# UpConverter.net
KiCad netlist of a schematic drawn in Altium Designer
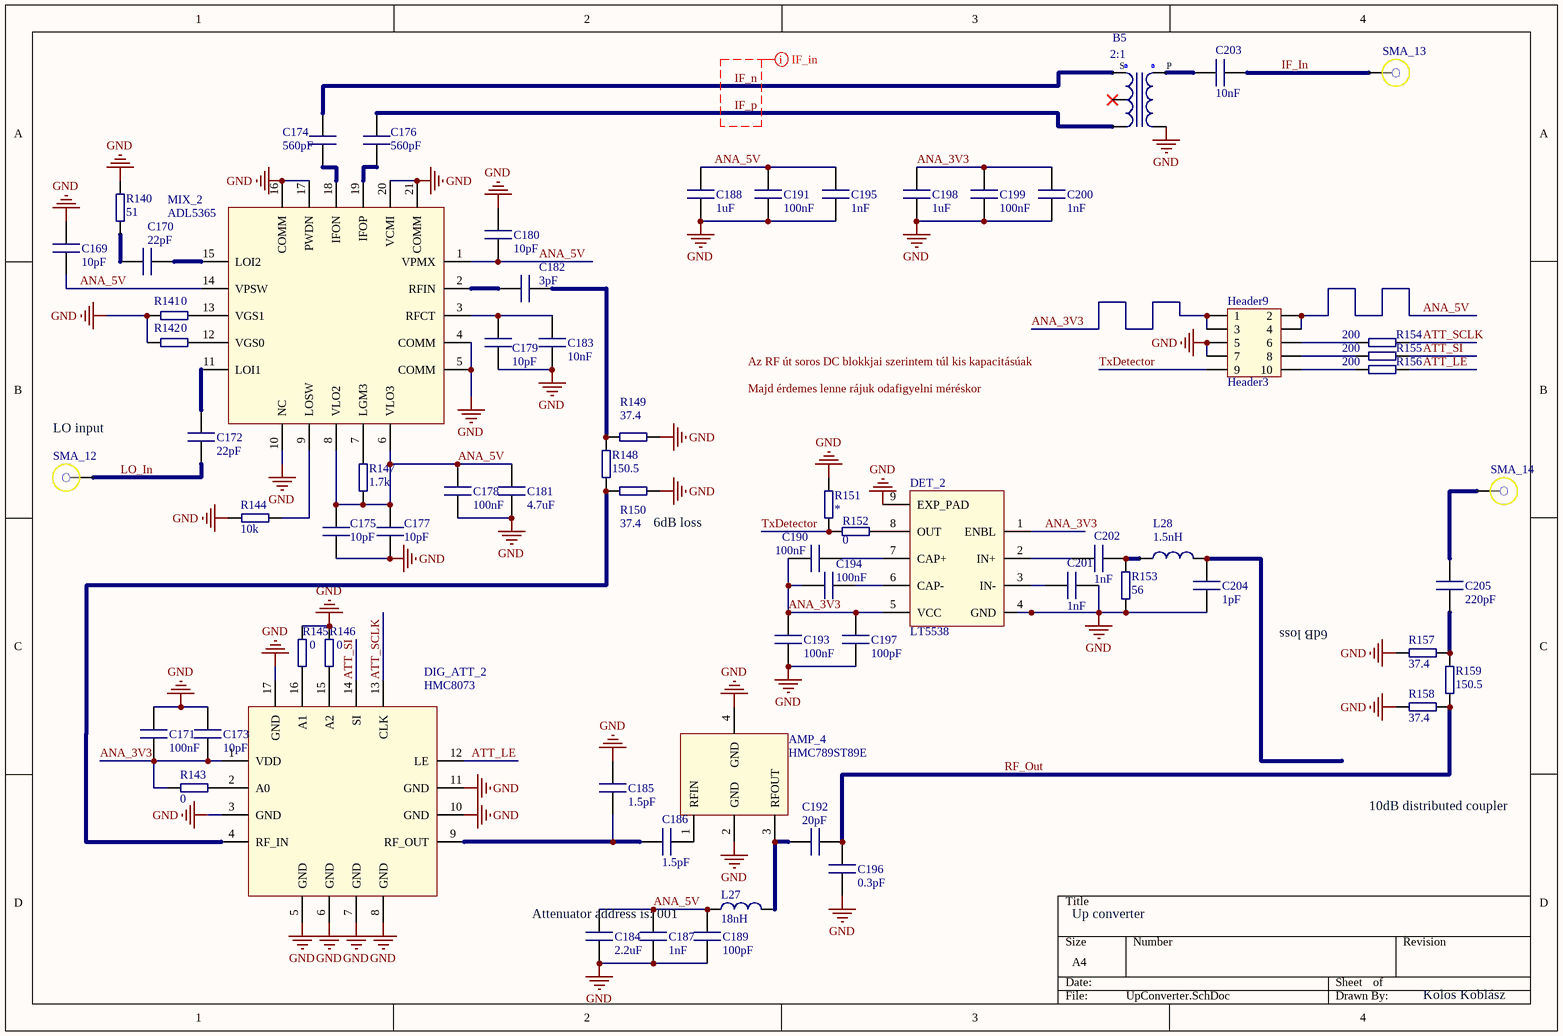
[diagram p0: UpConverter.SchDoc]

(export (version "E")
  (design (tool "Eeschema 10.0.6"))
  (components
    (comp (ref "AMP_4")
      (value "HMC789ST89E")
      (description "Gain Block MMIC")
      (fields (field (name "MANUFACTURER") "Analog Devices"))
      (libsource (lib "RadioProjectSchLib") (part "HMC789ST89E"))
    )
    (comp (ref "B5")
      (value "Balun")
      (footprint "Balun_Coil")
      (description "SMD Balun")
      (fields (field (name "IMPEDANCETRANSFORMATION P : S") "2:1"))
      (libsource (lib "RadioProjectSchLib") (part "Balun1"))
    )
    (comp (ref "C169")
      (value "10pF")
      (footprint "0805 SMD Passive")
      (description "SMD Capacitor")
      (fields (field (name "Comment") "Cap1"))
      (libsource (lib "RadioProjectSchLib") (part "Cap1"))
    )
    (comp (ref "C170")
      (value "22pF")
      (footprint "0805 SMD Passive")
      (description "SMD Capacitor")
      (fields (field (name "Comment") "Cap1"))
      (libsource (lib "RadioProjectSchLib") (part "Cap1"))
    )
    (comp (ref "C171")
      (value "100nF")
      (footprint "0805 SMD Passive")
      (description "SMD Capacitor")
      (fields (field (name "Comment") "Cap1"))
      (libsource (lib "RadioProjectSchLib") (part "Cap1"))
    )
    (comp (ref "C172")
      (value "22pF")
      (footprint "0805 SMD Passive")
      (description "SMD Capacitor")
      (fields (field (name "Comment") "Cap1"))
      (libsource (lib "RadioProjectSchLib") (part "Cap1"))
    )
    (comp (ref "C173")
      (value "10pF")
      (footprint "0805 SMD Passive")
      (description "SMD Capacitor")
      (fields (field (name "Comment") "Cap1"))
      (libsource (lib "RadioProjectSchLib") (part "Cap1"))
    )
    (comp (ref "C174")
      (value "560pF")
      (footprint "0805 SMD Passive")
      (description "SMD Capacitor")
      (fields (field (name "Comment") "Cap1"))
      (libsource (lib "RadioProjectSchLib") (part "Cap1"))
    )
    (comp (ref "C175")
      (value "10pF")
      (footprint "0805 SMD Passive")
      (description "SMD Capacitor")
      (fields (field (name "Comment") "Cap1"))
      (libsource (lib "RadioProjectSchLib") (part "Cap1"))
    )
    (comp (ref "C176")
      (value "560pF")
      (footprint "0805 SMD Passive")
      (description "SMD Capacitor")
      (fields (field (name "Comment") "Cap1"))
      (libsource (lib "RadioProjectSchLib") (part "Cap1"))
    )
    (comp (ref "C177")
      (value "10pF")
      (footprint "0805 SMD Passive")
      (description "SMD Capacitor")
      (fields (field (name "Comment") "Cap1"))
      (libsource (lib "RadioProjectSchLib") (part "Cap1"))
    )
    (comp (ref "C178")
      (value "100nF")
      (footprint "0805 SMD Passive")
      (description "SMD Capacitor")
      (fields (field (name "Comment") "Cap1"))
      (libsource (lib "RadioProjectSchLib") (part "Cap1"))
    )
    (comp (ref "C179")
      (value "10pF")
      (footprint "0805 SMD Passive")
      (description "SMD Capacitor")
      (fields (field (name "Comment") "Cap1"))
      (libsource (lib "RadioProjectSchLib") (part "Cap1"))
    )
    (comp (ref "C180")
      (value "10pF")
      (footprint "0805 SMD Passive")
      (description "SMD Capacitor")
      (fields (field (name "Comment") "Cap1"))
      (libsource (lib "RadioProjectSchLib") (part "Cap1"))
    )
    (comp (ref "C181")
      (value "4.7uF")
      (footprint "0805 SMD Passive")
      (description "SMD Capacitor")
      (fields (field (name "Comment") "Cap1"))
      (libsource (lib "RadioProjectSchLib") (part "Cap1"))
    )
    (comp (ref "C182")
      (value "3pF")
      (footprint "0805 SMD Passive")
      (description "SMD Capacitor")
      (fields (field (name "Comment") "Cap1"))
      (libsource (lib "RadioProjectSchLib") (part "Cap1"))
    )
    (comp (ref "C183")
      (value "10nF")
      (footprint "0805 SMD Passive")
      (description "SMD Capacitor")
      (fields (field (name "Comment") "Cap1"))
      (libsource (lib "RadioProjectSchLib") (part "Cap1"))
    )
    (comp (ref "C184")
      (value "2.2uF")
      (footprint "0805 SMD Passive")
      (description "SMD Capacitor")
      (fields (field (name "Comment") "Cap1"))
      (libsource (lib "RadioProjectSchLib") (part "Cap1"))
    )
    (comp (ref "C185")
      (value "1.5pF")
      (footprint "0805 SMD Passive")
      (description "SMD Capacitor")
      (fields (field (name "Comment") "Cap1"))
      (libsource (lib "RadioProjectSchLib") (part "Cap1"))
    )
    (comp (ref "C186")
      (value "1.5pF")
      (footprint "0805 SMD Passive")
      (description "SMD Capacitor")
      (fields (field (name "Comment") "Cap1"))
      (libsource (lib "RadioProjectSchLib") (part "Cap1"))
    )
    (comp (ref "C187")
      (value "1nF")
      (footprint "0805 SMD Passive")
      (description "SMD Capacitor")
      (fields (field (name "Comment") "Cap1"))
      (libsource (lib "RadioProjectSchLib") (part "Cap1"))
    )
    (comp (ref "C188")
      (value "1uF")
      (footprint "0805 SMD Passive")
      (description "SMD Capacitor")
      (fields (field (name "Comment") "Cap1"))
      (libsource (lib "RadioProjectSchLib") (part "Cap1"))
    )
    (comp (ref "C189")
      (value "100pF")
      (footprint "0805 SMD Passive")
      (description "SMD Capacitor")
      (fields (field (name "Comment") "Cap1"))
      (libsource (lib "RadioProjectSchLib") (part "Cap1"))
    )
    (comp (ref "C190")
      (value "100nF")
      (footprint "0805 SMD Passive")
      (description "SMD Capacitor")
      (fields (field (name "Comment") "Cap1"))
      (libsource (lib "RadioProjectSchLib") (part "Cap1"))
    )
    (comp (ref "C191")
      (value "100nF")
      (footprint "0805 SMD Passive")
      (description "SMD Capacitor")
      (fields (field (name "Comment") "Cap1"))
      (libsource (lib "RadioProjectSchLib") (part "Cap1"))
    )
    (comp (ref "C192")
      (value "20pF")
      (footprint "0805 SMD Passive")
      (description "SMD Capacitor")
      (fields (field (name "Comment") "Cap1"))
      (libsource (lib "RadioProjectSchLib") (part "Cap1"))
    )
    (comp (ref "C193")
      (value "100nF")
      (footprint "0805 SMD Passive")
      (description "SMD Capacitor")
      (fields (field (name "Comment") "Cap1"))
      (libsource (lib "RadioProjectSchLib") (part "Cap1"))
    )
    (comp (ref "C194")
      (value "100nF")
      (footprint "0805 SMD Passive")
      (description "SMD Capacitor")
      (fields (field (name "Comment") "Cap1"))
      (libsource (lib "RadioProjectSchLib") (part "Cap1"))
    )
    (comp (ref "C195")
      (value "1nF")
      (footprint "0805 SMD Passive")
      (description "SMD Capacitor")
      (fields (field (name "Comment") "Cap1"))
      (libsource (lib "RadioProjectSchLib") (part "Cap1"))
    )
    (comp (ref "C196")
      (value "0.3pF")
      (footprint "0805 SMD Passive")
      (description "SMD Capacitor")
      (fields (field (name "Comment") "Cap1"))
      (libsource (lib "RadioProjectSchLib") (part "Cap1"))
    )
    (comp (ref "C197")
      (value "100pF")
      (footprint "0805 SMD Passive")
      (description "SMD Capacitor")
      (fields (field (name "Comment") "Cap1"))
      (libsource (lib "RadioProjectSchLib") (part "Cap1"))
    )
    (comp (ref "C198")
      (value "1uF")
      (footprint "0805 SMD Passive")
      (description "SMD Capacitor")
      (fields (field (name "Comment") "Cap1"))
      (libsource (lib "RadioProjectSchLib") (part "Cap1"))
    )
    (comp (ref "C199")
      (value "100nF")
      (footprint "0805 SMD Passive")
      (description "SMD Capacitor")
      (fields (field (name "Comment") "Cap1"))
      (libsource (lib "RadioProjectSchLib") (part "Cap1"))
    )
    (comp (ref "C200")
      (value "1nF")
      (footprint "0805 SMD Passive")
      (description "SMD Capacitor")
      (fields (field (name "Comment") "Cap1"))
      (libsource (lib "RadioProjectSchLib") (part "Cap1"))
    )
    (comp (ref "C201")
      (value "1nF")
      (footprint "0805 SMD Passive")
      (description "SMD Capacitor")
      (fields (field (name "Comment") "Cap1"))
      (libsource (lib "RadioProjectSchLib") (part "Cap1"))
    )
    (comp (ref "C202")
      (value "1nF")
      (footprint "0805 SMD Passive")
      (description "SMD Capacitor")
      (fields (field (name "Comment") "Cap1"))
      (libsource (lib "RadioProjectSchLib") (part "Cap1"))
    )
    (comp (ref "C203")
      (value "10nF")
      (footprint "0805 SMD Passive")
      (description "SMD Capacitor")
      (fields (field (name "Comment") "Cap1"))
      (libsource (lib "RadioProjectSchLib") (part "Cap1"))
    )
    (comp (ref "C204")
      (value "1pF")
      (footprint "0805 SMD Passive")
      (description "SMD Capacitor")
      (fields (field (name "Comment") "Cap1"))
      (libsource (lib "RadioProjectSchLib") (part "Cap1"))
    )
    (comp (ref "C205")
      (value "220pF")
      (footprint "0805 SMD Passive")
      (description "SMD Capacitor")
      (fields (field (name "Comment") "Cap1"))
      (libsource (lib "RadioProjectSchLib") (part "Cap1"))
    )
    (comp (ref "DET_2")
      (value "LT5538")
      (description "Detector")
      (fields (field (name "MANUFACTURER") "Analog Devices"))
      (libsource (lib "RadioProjectSchLib") (part "LT5538"))
    )
    (comp (ref "DIG_ATT_2")
      (value "HMC8073")
      (description "Digital Attenuator")
      (fields (field (name "MANUFACTURER") "Analog Devices"))
      (libsource (lib "RadioProjectSchLib") (part "HMC8073"))
    )
    (comp (ref "Header9")
      (value "Header3")
      (footprint "Header3")
      (description "10 pin DIL header")
      (libsource (lib "RadioProjectSchLib") (part "Header3"))
    )
    (comp (ref "L27")
      (value "18nH")
      (footprint "0805 SMD Passive")
      (description "SMD Inductor")
      (fields (field (name "Comment") "Inductor"))
      (libsource (lib "RadioProjectSchLib") (part "Ind1"))
    )
    (comp (ref "L28")
      (value "1.5nH")
      (footprint "0805 SMD Passive")
      (description "SMD Inductor")
      (fields (field (name "Comment") "Inductor"))
      (libsource (lib "RadioProjectSchLib") (part "Ind1"))
    )
    (comp (ref "MIX_2")
      (value "ADL5365")
      (description "RF Mixer")
      (fields (field (name "MANUFACTURER") "Analog Devices"))
      (libsource (lib "RadioProjectSchLib") (part "ADL5365"))
    )
    (comp (ref "R140")
      (value "51")
      (footprint "0805 SMD Passive")
      (description "SMD Resistor")
      (fields (field (name "Comment") "Resistor"))
      (libsource (lib "RadioProjectSchLib") (part "Res1"))
    )
    (comp (ref "R141")
      (value "0")
      (footprint "0805 SMD Passive")
      (description "SMD Resistor")
      (fields (field (name "Comment") "Resistor"))
      (libsource (lib "RadioProjectSchLib") (part "Res1"))
    )
    (comp (ref "R142")
      (value "0")
      (footprint "0805 SMD Passive")
      (description "SMD Resistor")
      (fields (field (name "Comment") "Resistor"))
      (libsource (lib "RadioProjectSchLib") (part "Res1"))
    )
    (comp (ref "R143")
      (value "0")
      (footprint "0805 SMD Passive")
      (description "SMD Resistor")
      (fields (field (name "Comment") "Resistor"))
      (libsource (lib "RadioProjectSchLib") (part "Res1"))
    )
    (comp (ref "R144")
      (value "10k")
      (footprint "0805 SMD Passive")
      (description "SMD Resistor")
      (fields (field (name "Comment") "Resistor"))
      (libsource (lib "RadioProjectSchLib") (part "Res1"))
    )
    (comp (ref "R145")
      (value "0")
      (footprint "0805 SMD Passive")
      (description "SMD Resistor")
      (fields (field (name "Comment") "Resistor"))
      (libsource (lib "RadioProjectSchLib") (part "Res1"))
    )
    (comp (ref "R146")
      (value "0")
      (footprint "0805 SMD Passive")
      (description "SMD Resistor")
      (fields (field (name "Comment") "Resistor"))
      (libsource (lib "RadioProjectSchLib") (part "Res1"))
    )
    (comp (ref "R147")
      (value "1.7k")
      (footprint "0805 SMD Passive")
      (description "SMD Resistor")
      (fields (field (name "Comment") "Resistor"))
      (libsource (lib "RadioProjectSchLib") (part "Res1"))
    )
    (comp (ref "R148")
      (value "150.5")
      (footprint "0805 SMD Passive")
      (description "SMD Resistor")
      (fields (field (name "Comment") "Resistor"))
      (libsource (lib "RadioProjectSchLib") (part "Res1"))
    )
    (comp (ref "R149")
      (value "37.4")
      (footprint "0805 SMD Passive")
      (description "SMD Resistor")
      (fields (field (name "Comment") "Resistor"))
      (libsource (lib "RadioProjectSchLib") (part "Res1"))
    )
    (comp (ref "R150")
      (value "37.4")
      (footprint "0805 SMD Passive")
      (description "SMD Resistor")
      (fields (field (name "Comment") "Resistor"))
      (libsource (lib "RadioProjectSchLib") (part "Res1"))
    )
    (comp (ref "R151")
      (value "Resistor")
      (footprint "0805 SMD Passive")
      (description "SMD Resistor")
      (fields (field (name "ALTIUM_VALUE") "*"))
      (libsource (lib "RadioProjectSchLib") (part "Res1"))
    )
    (comp (ref "R152")
      (value "0")
      (footprint "0805 SMD Passive")
      (description "SMD Resistor")
      (fields (field (name "Comment") "Resistor"))
      (libsource (lib "RadioProjectSchLib") (part "Res1"))
    )
    (comp (ref "R153")
      (value "56")
      (footprint "0805 SMD Passive")
      (description "SMD Resistor")
      (fields (field (name "Comment") "Resistor"))
      (libsource (lib "RadioProjectSchLib") (part "Res1"))
    )
    (comp (ref "R154")
      (value "200")
      (footprint "0805 SMD Passive")
      (description "SMD Resistor")
      (fields (field (name "Comment") "Resistor"))
      (libsource (lib "RadioProjectSchLib") (part "Res1"))
    )
    (comp (ref "R155")
      (value "200")
      (footprint "0805 SMD Passive")
      (description "SMD Resistor")
      (fields (field (name "Comment") "Resistor"))
      (libsource (lib "RadioProjectSchLib") (part "Res1"))
    )
    (comp (ref "R156")
      (value "200")
      (footprint "0805 SMD Passive")
      (description "SMD Resistor")
      (fields (field (name "Comment") "Resistor"))
      (libsource (lib "RadioProjectSchLib") (part "Res1"))
    )
    (comp (ref "R157")
      (value "37.4")
      (footprint "0805 SMD Passive")
      (description "SMD Resistor")
      (fields (field (name "Comment") "Resistor"))
      (libsource (lib "RadioProjectSchLib") (part "Res1"))
    )
    (comp (ref "R158")
      (value "37.4")
      (footprint "0805 SMD Passive")
      (description "SMD Resistor")
      (fields (field (name "Comment") "Resistor"))
      (libsource (lib "RadioProjectSchLib") (part "Res1"))
    )
    (comp (ref "R159")
      (value "150.5")
      (footprint "0805 SMD Passive")
      (description "SMD Resistor")
      (fields (field (name "Comment") "Resistor"))
      (libsource (lib "RadioProjectSchLib") (part "Res1"))
    )
    (comp (ref "SMA_12")
      (value "SMA1")
      (footprint "SMA Flange")
      (description "SMA Female")
      (libsource (lib "RadioProjectSchLib") (part "SMA1"))
    )
    (comp (ref "SMA_13")
      (value "SMA1")
      (footprint "SMA Flange")
      (description "SMA Female")
      (libsource (lib "RadioProjectSchLib") (part "SMA1"))
    )
    (comp (ref "SMA_14")
      (value "SMA1")
      (footprint "SMA Flange")
      (description "SMA Female")
      (libsource (lib "RadioProjectSchLib") (part "SMA1"))
    )
  )
  (nets
    (net (code "1") (name "/ANA_3V3") (class "Default")
      (node (ref "C171") (pin "1") (pinfunction "*_1") (pintype "passive"))
      (node (ref "C173") (pin "1") (pinfunction "*_1") (pintype "passive"))
      (node (ref "C190") (pin "2") (pinfunction "*_2") (pintype "passive"))
      (node (ref "C193") (pin "1") (pinfunction "*_1") (pintype "passive"))
      (node (ref "C194") (pin "2") (pinfunction "*_2") (pintype "passive"))
      (node (ref "C197") (pin "1") (pinfunction "*_1") (pintype "passive"))
      (node (ref "C198") (pin "2") (pinfunction "*_2") (pintype "passive"))
      (node (ref "C199") (pin "2") (pinfunction "*_2") (pintype "passive"))
      (node (ref "C200") (pin "2") (pinfunction "*_2") (pintype "passive"))
      (node (ref "DET_2") (pin "1") (pinfunction "ENBL_1") (pintype "passive"))
      (node (ref "DET_2") (pin "5") (pinfunction "VCC_5") (pintype "passive"))
      (node (ref "DIG_ATT_2") (pin "1") (pinfunction "VDD_1") (pintype "passive"))
      (node (ref "Header9") (pin "1") (pinfunction "1_1") (pintype "passive"))
      (node (ref "Header9") (pin "3") (pinfunction "3_3") (pintype "passive"))
      (node (ref "R143") (pin "2") (pinfunction "*_2") (pintype "passive"))
    )
    (net (code "2") (name "/ANA_5V") (class "Default")
      (node (ref "C169") (pin "2") (pinfunction "*_2") (pintype "passive"))
      (node (ref "C175") (pin "2") (pinfunction "*_2") (pintype "passive"))
      (node (ref "C177") (pin "1") (pinfunction "*_1") (pintype "passive"))
      (node (ref "C178") (pin "2") (pinfunction "*_2") (pintype "passive"))
      (node (ref "C180") (pin "2") (pinfunction "*_2") (pintype "passive"))
      (node (ref "C181") (pin "2") (pinfunction "*_2") (pintype "passive"))
      (node (ref "C184") (pin "1") (pinfunction "*_1") (pintype "passive"))
      (node (ref "C187") (pin "1") (pinfunction "*_1") (pintype "passive"))
      (node (ref "C188") (pin "2") (pinfunction "*_2") (pintype "passive"))
      (node (ref "C189") (pin "1") (pinfunction "*_1") (pintype "passive"))
      (node (ref "C191") (pin "2") (pinfunction "*_2") (pintype "passive"))
      (node (ref "C195") (pin "2") (pinfunction "*_2") (pintype "passive"))
      (node (ref "Header9") (pin "2") (pinfunction "2_2") (pintype "passive"))
      (node (ref "Header9") (pin "4") (pinfunction "4_4") (pintype "passive"))
      (node (ref "L27") (pin "2") (pinfunction "*_2") (pintype "passive"))
      (node (ref "MIX_2") (pin "1") (pinfunction "VPMX_1") (pintype "passive"))
      (node (ref "MIX_2") (pin "14") (pinfunction "VPSW_14") (pintype "passive"))
      (node (ref "MIX_2") (pin "6") (pinfunction "VLO3_6") (pintype "passive"))
      (node (ref "MIX_2") (pin "8") (pinfunction "VLO2_8") (pintype "passive"))
      (node (ref "R147") (pin "1") (pinfunction "*_1") (pintype "passive"))
    )
    (net (code "3") (name "/ATT_LE") (class "Default")
      (node (ref "DIG_ATT_2") (pin "12") (pinfunction "LE_12") (pintype "passive"))
      (node (ref "R156") (pin "1") (pinfunction "*_1") (pintype "passive"))
    )
    (net (code "4") (name "/ATT_SCLK") (class "Default")
      (node (ref "DIG_ATT_2") (pin "13") (pinfunction "CLK_13") (pintype "passive"))
      (node (ref "R154") (pin "1") (pinfunction "*_1") (pintype "passive"))
    )
    (net (code "5") (name "/ATT_SI") (class "Default")
      (node (ref "DIG_ATT_2") (pin "14") (pinfunction "SI_14") (pintype "passive"))
      (node (ref "R155") (pin "1") (pinfunction "*_1") (pintype "passive"))
    )
    (net (code "7") (name "/IF_In") (class "Default")
      (node (ref "C203") (pin "1") (pinfunction "*_1") (pintype "passive"))
      (node (ref "SMA_13") (pin "1") (pinfunction "1_1") (pintype "passive"))
    )
    (net (code "8") (name "/IF_n") (class "Default")
      (node (ref "B5") (pin "1") (pinfunction "1_1") (pintype "passive"))
      (node (ref "C174") (pin "1") (pinfunction "*_1") (pintype "passive"))
    )
    (net (code "9") (name "/IF_p") (class "Default")
      (node (ref "B5") (pin "3") (pinfunction "3_3") (pintype "passive"))
      (node (ref "C176") (pin "1") (pinfunction "*_1") (pintype "passive"))
    )
    (net (code "10") (name "/LO_In") (class "Default")
      (node (ref "C172") (pin "1") (pinfunction "*_1") (pintype "passive"))
      (node (ref "SMA_12") (pin "1") (pinfunction "1_1") (pintype "passive"))
    )
    (net (code "12") (name "/RF_Out") (class "Default")
      (node (ref "C192") (pin "2") (pinfunction "*_2") (pintype "passive"))
      (node (ref "C196") (pin "1") (pinfunction "*_1") (pintype "passive"))
      (node (ref "R158") (pin "1") (pinfunction "*_1") (pintype "passive"))
      (node (ref "R159") (pin "2") (pinfunction "*_2") (pintype "passive"))
    )
    (net (code "13") (name "/TxDetector") (class "Default")
      (node (ref "Header9") (pin "9") (pinfunction "9_9") (pintype "passive"))
      (node (ref "R151") (pin "1") (pinfunction "*_1") (pintype "passive"))
      (node (ref "R152") (pin "1") (pinfunction "*_1") (pintype "passive"))
    )
    (net (code "14") (name "GND") (class "Default")
      (node (ref "AMP_4") (pin "2") (pinfunction "GND_2") (pintype "passive"))
      (node (ref "AMP_4") (pin "4") (pinfunction "GND_4") (pintype "passive"))
      (node (ref "B5") (pin "4") (pinfunction "4_4") (pintype "passive"))
      (node (ref "C169") (pin "1") (pinfunction "*_1") (pintype "passive"))
      (node (ref "C171") (pin "2") (pinfunction "*_2") (pintype "passive"))
      (node (ref "C173") (pin "2") (pinfunction "*_2") (pintype "passive"))
      (node (ref "C175") (pin "1") (pinfunction "*_1") (pintype "passive"))
      (node (ref "C177") (pin "2") (pinfunction "*_2") (pintype "passive"))
      (node (ref "C178") (pin "1") (pinfunction "*_1") (pintype "passive"))
      (node (ref "C179") (pin "1") (pinfunction "*_1") (pintype "passive"))
      (node (ref "C180") (pin "1") (pinfunction "*_1") (pintype "passive"))
      (node (ref "C181") (pin "1") (pinfunction "*_1") (pintype "passive"))
      (node (ref "C183") (pin "1") (pinfunction "*_1") (pintype "passive"))
      (node (ref "C184") (pin "2") (pinfunction "*_2") (pintype "passive"))
      (node (ref "C185") (pin "1") (pinfunction "*_1") (pintype "passive"))
      (node (ref "C187") (pin "2") (pinfunction "*_2") (pintype "passive"))
      (node (ref "C188") (pin "1") (pinfunction "*_1") (pintype "passive"))
      (node (ref "C189") (pin "2") (pinfunction "*_2") (pintype "passive"))
      (node (ref "C191") (pin "1") (pinfunction "*_1") (pintype "passive"))
      (node (ref "C193") (pin "2") (pinfunction "*_2") (pintype "passive"))
      (node (ref "C195") (pin "1") (pinfunction "*_1") (pintype "passive"))
      (node (ref "C196") (pin "2") (pinfunction "*_2") (pintype "passive"))
      (node (ref "C197") (pin "2") (pinfunction "*_2") (pintype "passive"))
      (node (ref "C198") (pin "1") (pinfunction "*_1") (pintype "passive"))
      (node (ref "C199") (pin "1") (pinfunction "*_1") (pintype "passive"))
      (node (ref "C200") (pin "1") (pinfunction "*_1") (pintype "passive"))
      (node (ref "C201") (pin "1") (pinfunction "*_1") (pintype "passive"))
      (node (ref "C204") (pin "1") (pinfunction "*_1") (pintype "passive"))
      (node (ref "DET_2") (pin "4") (pinfunction "GND_4") (pintype "passive"))
      (node (ref "DET_2") (pin "9") (pinfunction "EXP_PAD_9") (pintype "passive"))
      (node (ref "DIG_ATT_2") (pin "10") (pinfunction "GND_10") (pintype "passive"))
      (node (ref "DIG_ATT_2") (pin "11") (pinfunction "GND_11") (pintype "passive"))
      (node (ref "DIG_ATT_2") (pin "17") (pinfunction "GND_17") (pintype "passive"))
      (node (ref "DIG_ATT_2") (pin "3") (pinfunction "GND_3") (pintype "passive"))
      (node (ref "DIG_ATT_2") (pin "5") (pinfunction "GND_5") (pintype "passive"))
      (node (ref "DIG_ATT_2") (pin "6") (pinfunction "GND_6") (pintype "passive"))
      (node (ref "DIG_ATT_2") (pin "7") (pinfunction "GND_7") (pintype "passive"))
      (node (ref "DIG_ATT_2") (pin "8") (pinfunction "GND_8") (pintype "passive"))
      (node (ref "Header9") (pin "5") (pinfunction "5_5") (pintype "passive"))
      (node (ref "Header9") (pin "7") (pinfunction "7_7") (pintype "passive"))
      (node (ref "MIX_2") (pin "10") (pinfunction "NC_10") (pintype "passive"))
      (node (ref "MIX_2") (pin "16") (pinfunction "COMM_16") (pintype "passive"))
      (node (ref "MIX_2") (pin "17") (pinfunction "PWDN_17") (pintype "passive"))
      (node (ref "MIX_2") (pin "20") (pinfunction "VCMI_20") (pintype "passive"))
      (node (ref "MIX_2") (pin "21") (pinfunction "COMM_21") (pintype "passive"))
      (node (ref "MIX_2") (pin "4") (pinfunction "COMM_4") (pintype "passive"))
      (node (ref "MIX_2") (pin "5") (pinfunction "COMM_5") (pintype "passive"))
      (node (ref "R140") (pin "1") (pinfunction "*_1") (pintype "passive"))
      (node (ref "R141") (pin "2") (pinfunction "*_2") (pintype "passive"))
      (node (ref "R142") (pin "2") (pinfunction "*_2") (pintype "passive"))
      (node (ref "R144") (pin "2") (pinfunction "*_2") (pintype "passive"))
      (node (ref "R145") (pin "2") (pinfunction "*_2") (pintype "passive"))
      (node (ref "R146") (pin "2") (pinfunction "*_2") (pintype "passive"))
      (node (ref "R149") (pin "2") (pinfunction "*_2") (pintype "passive"))
      (node (ref "R150") (pin "2") (pinfunction "*_2") (pintype "passive"))
      (node (ref "R151") (pin "2") (pinfunction "*_2") (pintype "passive"))
      (node (ref "R153") (pin "1") (pinfunction "*_1") (pintype "passive"))
      (node (ref "R157") (pin "2") (pinfunction "*_2") (pintype "passive"))
      (node (ref "R158") (pin "2") (pinfunction "*_2") (pintype "passive"))
    )
    (net (code "15") (name "Net-(AMP_4-RFIN)") (class "Default")
      (node (ref "AMP_4") (pin "1") (pinfunction "RFIN_1") (pintype "passive"))
      (node (ref "C186") (pin "2") (pinfunction "*_2") (pintype "passive"))
    )
    (net (code "16") (name "Net-(AMP_4-RFOUT)") (class "Default")
      (node (ref "AMP_4") (pin "3") (pinfunction "RFOUT_3") (pintype "passive"))
      (node (ref "C192") (pin "1") (pinfunction "*_1") (pintype "passive"))
      (node (ref "L27") (pin "1") (pinfunction "*_1") (pintype "passive"))
    )
    (net (code "17") (name "Net-(B5-Pad5)") (class "Default")
      (node (ref "B5") (pin "5") (pinfunction "5_5") (pintype "passive"))
      (node (ref "C203") (pin "2") (pinfunction "*_2") (pintype "passive"))
    )
    (net (code "18") (name "Net-(C170-*-Pad1)") (class "Default")
      (node (ref "C170") (pin "1") (pinfunction "*_1") (pintype "passive"))
      (node (ref "R140") (pin "2") (pinfunction "*_2") (pintype "passive"))
    )
    (net (code "19") (name "Net-(C182-*-Pad1)") (class "Default")
      (node (ref "C182") (pin "1") (pinfunction "*_1") (pintype "passive"))
      (node (ref "R148") (pin "1") (pinfunction "*_1") (pintype "passive"))
      (node (ref "R149") (pin "1") (pinfunction "*_1") (pintype "passive"))
    )
    (net (code "20") (name "Net-(C202-*-Pad1)") (class "Default")
      (node (ref "C202") (pin "1") (pinfunction "*_1") (pintype "passive"))
      (node (ref "L28") (pin "2") (pinfunction "*_2") (pintype "passive"))
      (node (ref "R153") (pin "2") (pinfunction "*_2") (pintype "passive"))
    )
    (net (code "21") (name "Net-(C204-*-Pad2)") (class "Default")
      (node (ref "C204") (pin "2") (pinfunction "*_2") (pintype "passive"))
      (node (ref "L28") (pin "1") (pinfunction "*_1") (pintype "passive"))
    )
    (net (code "22") (name "Net-(C205-*-Pad1)") (class "Default")
      (node (ref "C205") (pin "1") (pinfunction "*_1") (pintype "passive"))
      (node (ref "R157") (pin "1") (pinfunction "*_1") (pintype "passive"))
      (node (ref "R159") (pin "1") (pinfunction "*_1") (pintype "passive"))
    )
    (net (code "23") (name "Net-(C205-*-Pad2)") (class "Default")
      (node (ref "C205") (pin "2") (pinfunction "*_2") (pintype "passive"))
      (node (ref "SMA_14") (pin "1") (pinfunction "1_1") (pintype "passive"))
    )
    (net (code "24") (name "Net-(DET_2-CAP+)") (class "Default")
      (node (ref "C190") (pin "1") (pinfunction "*_1") (pintype "passive"))
      (node (ref "DET_2") (pin "7") (pinfunction "CAP+_7") (pintype "passive"))
    )
    (net (code "25") (name "Net-(DET_2-CAP-)") (class "Default")
      (node (ref "C194") (pin "1") (pinfunction "*_1") (pintype "passive"))
      (node (ref "DET_2") (pin "6") (pinfunction "CAP-_6") (pintype "passive"))
    )
    (net (code "26") (name "Net-(DET_2-IN+)") (class "Default")
      (node (ref "C202") (pin "2") (pinfunction "*_2") (pintype "passive"))
      (node (ref "DET_2") (pin "2") (pinfunction "IN+_2") (pintype "passive"))
    )
    (net (code "27") (name "Net-(DET_2-IN-)") (class "Default")
      (node (ref "C201") (pin "2") (pinfunction "*_2") (pintype "passive"))
      (node (ref "DET_2") (pin "3") (pinfunction "IN-_3") (pintype "passive"))
    )
    (net (code "28") (name "Net-(DET_2-OUT)") (class "Default")
      (node (ref "DET_2") (pin "8") (pinfunction "OUT_8") (pintype "passive"))
      (node (ref "R152") (pin "2") (pinfunction "*_2") (pintype "passive"))
    )
    (net (code "29") (name "Net-(DIG_ATT_2-A0)") (class "Default")
      (node (ref "DIG_ATT_2") (pin "2") (pinfunction "A0_2") (pintype "passive"))
      (node (ref "R143") (pin "1") (pinfunction "*_1") (pintype "passive"))
    )
    (net (code "30") (name "Net-(DIG_ATT_2-A1)") (class "Default")
      (node (ref "DIG_ATT_2") (pin "16") (pinfunction "A1_16") (pintype "passive"))
      (node (ref "R145") (pin "1") (pinfunction "*_1") (pintype "passive"))
    )
    (net (code "31") (name "Net-(DIG_ATT_2-A2)") (class "Default")
      (node (ref "DIG_ATT_2") (pin "15") (pinfunction "A2_15") (pintype "passive"))
      (node (ref "R146") (pin "1") (pinfunction "*_1") (pintype "passive"))
    )
    (net (code "32") (name "Net-(DIG_ATT_2-RF_IN)") (class "Default")
      (node (ref "DIG_ATT_2") (pin "4") (pinfunction "RF_IN_4") (pintype "passive"))
      (node (ref "R148") (pin "2") (pinfunction "*_2") (pintype "passive"))
      (node (ref "R150") (pin "1") (pinfunction "*_1") (pintype "passive"))
    )
    (net (code "33") (name "Net-(DIG_ATT_2-RF_OUT)") (class "Default")
      (node (ref "C185") (pin "2") (pinfunction "*_2") (pintype "passive"))
      (node (ref "C186") (pin "1") (pinfunction "*_1") (pintype "passive"))
      (node (ref "DIG_ATT_2") (pin "9") (pinfunction "RF_OUT_9") (pintype "passive"))
    )
    (net (code "34") (name "Net-(Header9-Pad6)") (class "Default")
      (node (ref "Header9") (pin "6") (pinfunction "6_6") (pintype "passive"))
      (node (ref "R154") (pin "2") (pinfunction "*_2") (pintype "passive"))
    )
    (net (code "35") (name "Net-(Header9-Pad8)") (class "Default")
      (node (ref "Header9") (pin "8") (pinfunction "8_8") (pintype "passive"))
      (node (ref "R155") (pin "2") (pinfunction "*_2") (pintype "passive"))
    )
    (net (code "36") (name "Net-(Header9-Pad10)") (class "Default")
      (node (ref "Header9") (pin "10") (pinfunction "10_10") (pintype "passive"))
      (node (ref "R156") (pin "2") (pinfunction "*_2") (pintype "passive"))
    )
    (net (code "37") (name "Net-(MIX_2-IFON)") (class "Default")
      (node (ref "C174") (pin "2") (pinfunction "*_2") (pintype "passive"))
      (node (ref "MIX_2") (pin "18") (pinfunction "IFON_18") (pintype "passive"))
    )
    (net (code "38") (name "Net-(MIX_2-IFOP)") (class "Default")
      (node (ref "C176") (pin "2") (pinfunction "*_2") (pintype "passive"))
      (node (ref "MIX_2") (pin "19") (pinfunction "IFOP_19") (pintype "passive"))
    )
    (net (code "39") (name "Net-(MIX_2-LGM3)") (class "Default")
      (node (ref "MIX_2") (pin "7") (pinfunction "LGM3_7") (pintype "passive"))
      (node (ref "R147") (pin "2") (pinfunction "*_2") (pintype "passive"))
    )
    (net (code "40") (name "Net-(MIX_2-LOI1)") (class "Default")
      (node (ref "C172") (pin "2") (pinfunction "*_2") (pintype "passive"))
      (node (ref "MIX_2") (pin "11") (pinfunction "LOI1_11") (pintype "passive"))
    )
    (net (code "41") (name "Net-(MIX_2-LOI2)") (class "Default")
      (node (ref "C170") (pin "2") (pinfunction "*_2") (pintype "passive"))
      (node (ref "MIX_2") (pin "15") (pinfunction "LOI2_15") (pintype "passive"))
    )
    (net (code "42") (name "Net-(MIX_2-LOSW)") (class "Default")
      (node (ref "MIX_2") (pin "9") (pinfunction "LOSW_9") (pintype "passive"))
      (node (ref "R144") (pin "1") (pinfunction "*_1") (pintype "passive"))
    )
    (net (code "43") (name "Net-(MIX_2-RFCT)") (class "Default")
      (node (ref "C179") (pin "2") (pinfunction "*_2") (pintype "passive"))
      (node (ref "C183") (pin "2") (pinfunction "*_2") (pintype "passive"))
      (node (ref "MIX_2") (pin "3") (pinfunction "RFCT_3") (pintype "passive"))
    )
    (net (code "44") (name "Net-(MIX_2-RFIN)") (class "Default")
      (node (ref "C182") (pin "2") (pinfunction "*_2") (pintype "passive"))
      (node (ref "MIX_2") (pin "2") (pinfunction "RFIN_2") (pintype "passive"))
    )
    (net (code "45") (name "Net-(MIX_2-VGS0)") (class "Default")
      (node (ref "MIX_2") (pin "12") (pinfunction "VGS0_12") (pintype "passive"))
      (node (ref "R142") (pin "1") (pinfunction "*_1") (pintype "passive"))
    )
    (net (code "46") (name "Net-(MIX_2-VGS1)") (class "Default")
      (node (ref "MIX_2") (pin "13") (pinfunction "VGS1_13") (pintype "passive"))
      (node (ref "R141") (pin "1") (pinfunction "*_1") (pintype "passive"))
    )
    (net (code "47") (name "unconnected-(B5-Pad2)") (class "Default")
      (node (ref "B5") (pin "2") (pinfunction "2_2") (pintype "passive+no_connect"))
    )
  )
)
